# RescueMe.net
KiCad netlist of a schematic drawn in EAGLE
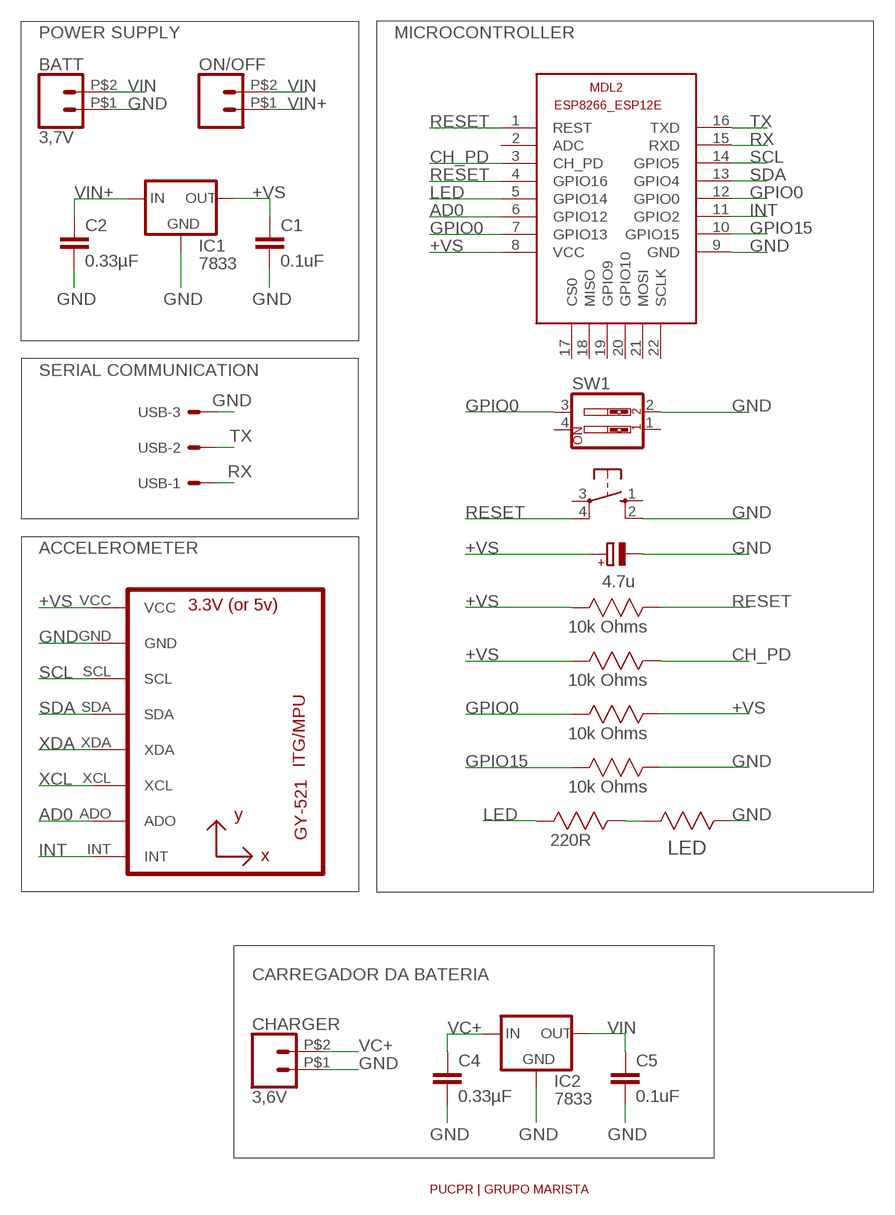
[diagram p0: schematic, sheet 1]

(export (version "E")
  (design (tool "Eeschema 10.0.6"))
  (components
    (comp (ref "BATT")
      (value "3,7V")
      (footprint "eagle-import:1X02_BIG")
      (libsource (lib "eagle-import") (part "CONN_02PTH2"))
    )
    (comp (ref "C1")
      (value "0.1uF")
      (footprint "eagle-import:0805")
      (libsource (lib "eagle-import") (part "0.33UF/330NF-0805-50V-10%"))
    )
    (comp (ref "C2")
      (value "0.33µF")
      (footprint "eagle-import:0805")
      (libsource (lib "eagle-import") (part "0.33UF/330NF-0805-50V-10%"))
    )
    (comp (ref "C4")
      (value "0.33µF")
      (footprint "eagle-import:0805")
      (libsource (lib "eagle-import") (part "0.33UF/330NF-0805-50V-10%"))
    )
    (comp (ref "C5")
      (value "0.1uF")
      (footprint "eagle-import:0805")
      (libsource (lib "eagle-import") (part "0.33UF/330NF-0805-50V-10%"))
    )
    (comp (ref "C7")
      (value "4.7u")
      (footprint "eagle-import:153CLV-0405")
      (libsource (lib "eagle-import") (part "CPOL-EU153CLV-0405"))
    )
    (comp (ref "CHARGER")
      (value "3,6V")
      (footprint "eagle-import:1X02_BIG")
      (libsource (lib "eagle-import") (part "CONN_02PTH2"))
    )
    (comp (ref "IC1")
      (value "7833")
      (footprint "eagle-import:78XXS")
      (libsource (lib "eagle-import") (part "78XXS"))
    )
    (comp (ref "IC2")
      (value "7833")
      (footprint "eagle-import:78XXS")
      (libsource (lib "eagle-import") (part "78XXS"))
    )
    (comp (ref "LED")
      (value "ERA-6AEB221V")
      (footprint "eagle-import:RESC2013X65N")
      (fields (field (name "TOLERANCE") "±0.1 %"))
      (libsource (lib "eagle-import") (part "ERA-6AEB221V"))
    )
    (comp (ref "MDL2")
      (value "ESP8266")
      (footprint "eagle-import:ESP8266-ESP12E")
      (fields (field (name "MPN") "317060015"))
      (libsource (lib "eagle-import") (part "ESP8266-12EESP8266-ESP12E"))
    )
    (comp (ref "ON/OFF")
      (value "CONN_02PTH2")
      (footprint "eagle-import:1X02_BIG")
      (libsource (lib "eagle-import") (part "CONN_02PTH2"))
    )
    (comp (ref "R_CHPD")
      (value "10k Ohms")
      (footprint "eagle-import:RESC2013X65N")
      (fields (field (name "MPN") "ERA6AEB103V") (field (name "TOLERANCE") "±0.1 %"))
      (libsource (lib "eagle-import") (part "ERA6AEB103V"))
    )
    (comp (ref "R_G0")
      (value "10k Ohms")
      (footprint "eagle-import:RESC2013X65N")
      (fields (field (name "MPN") "ERA6AEB103V") (field (name "TOLERANCE") "±0.1 %"))
      (libsource (lib "eagle-import") (part "ERA6AEB103V"))
    )
    (comp (ref "R_G15")
      (value "10k Ohms")
      (footprint "eagle-import:RESC2013X65N")
      (fields (field (name "MPN") "ERA6AEB103V") (field (name "TOLERANCE") "±0.1 %"))
      (libsource (lib "eagle-import") (part "ERA6AEB103V"))
    )
    (comp (ref "R_LED")
      (value "220R")
      (footprint "eagle-import:RESC2013X65N")
      (fields (field (name "MPN") "ERA-6AEB221V") (field (name "TOLERANCE") "±0.1 %"))
      (libsource (lib "eagle-import") (part "ERA-6AEB221V"))
    )
    (comp (ref "R_RST")
      (value "10k Ohms")
      (footprint "eagle-import:RESC2013X65N")
      (fields (field (name "MPN") "ERA6AEB103V") (field (name "TOLERANCE") "±0.1 %"))
      (libsource (lib "eagle-import") (part "ERA6AEB103V"))
    )
    (comp (ref "S1")
      (value "10-XX")
      (footprint "eagle-import:B3F-10XX")
      (fields (field (name "MPN") "B3F-1000"))
      (libsource (lib "eagle-import") (part "10-XX"))
    )
    (comp (ref "SW1")
      (value "SW_DIP-2")
      (footprint "eagle-import:DIPSWITCH-02")
      (libsource (lib "eagle-import") (part "SW_DIP-2"))
    )
    (comp (ref "U$1")
      (value "PUCPR_G")
      (footprint "eagle-import:PUCPR")
      (libsource (lib "eagle-import") (part "PUCPR_G"))
    )
    (comp (ref "U1")
      (value "GY-521MPU6050")
      (footprint "eagle-import:GY-521")
      (libsource (lib "eagle-import") (part "GY-521MPU6050"))
    )
    (comp (ref "USB")
      (value "22-27-2031-03")
      (footprint "eagle-import:6410-03")
      (libsource (lib "eagle-import") (part "22-?-0327-2031"))
    )
  )
  (nets
    (net (code "1") (name "/+VS") (class "Default")
      (node (ref "C1") (pin "1") (pinfunction "1_1") (pintype "passive"))
      (node (ref "C7") (pin "+") (pinfunction "+_+") (pintype "passive"))
      (node (ref "IC1") (pin "OUT") (pinfunction "OUT_OUT") (pintype "passive"))
      (node (ref "MDL2") (pin "8") (pinfunction "VCC_8") (pintype "bidirectional"))
      (node (ref "R_CHPD") (pin "2") (pinfunction "R2_2") (pintype "passive"))
      (node (ref "R_G0") (pin "1") (pinfunction "R1_1") (pintype "passive"))
      (node (ref "R_RST") (pin "2") (pinfunction "R2_2") (pintype "passive"))
      (node (ref "U1") (pin "VCC") (pinfunction "VCC_VCC") (pintype "bidirectional"))
    )
    (net (code "2") (name "/AD0") (class "Default")
      (node (ref "MDL2") (pin "6") (pinfunction "GPIO12_6") (pintype "bidirectional"))
      (node (ref "U1") (pin "ADO") (pinfunction "ADO_ADO") (pintype "bidirectional"))
    )
    (net (code "3") (name "/CH_PD") (class "Default")
      (node (ref "MDL2") (pin "3") (pinfunction "CH_PD_3") (pintype "bidirectional"))
      (node (ref "R_CHPD") (pin "1") (pinfunction "R1_1") (pintype "passive"))
    )
    (net (code "4") (name "/GND") (class "Default")
      (node (ref "BATT") (pin "P$1") (pinfunction "1_P$1") (pintype "passive"))
      (node (ref "C1") (pin "2") (pinfunction "2_2") (pintype "passive"))
      (node (ref "C2") (pin "2") (pinfunction "2_2") (pintype "passive"))
      (node (ref "C4") (pin "2") (pinfunction "2_2") (pintype "passive"))
      (node (ref "C5") (pin "2") (pinfunction "2_2") (pintype "passive"))
      (node (ref "C7") (pin "-") (pinfunction "-_-") (pintype "passive"))
      (node (ref "CHARGER") (pin "P$1") (pinfunction "1_P$1") (pintype "passive"))
      (node (ref "IC1") (pin "GND") (pinfunction "GND_GND") (pintype "input"))
      (node (ref "IC2") (pin "GND") (pinfunction "GND_GND") (pintype "input"))
      (node (ref "LED") (pin "1") (pinfunction "R1_1") (pintype "passive"))
      (node (ref "MDL2") (pin "9") (pinfunction "GND_9") (pintype "bidirectional"))
      (node (ref "R_G15") (pin "1") (pinfunction "R1_1") (pintype "passive"))
      (node (ref "S1") (pin "2") (pinfunction "S1_2") (pintype "passive"))
      (node (ref "SW1") (pin "2") (pinfunction "2_2") (pintype "passive"))
      (node (ref "U1") (pin "GND") (pinfunction "GND_GND") (pintype "bidirectional"))
      (node (ref "USB") (pin "3") (pinfunction "S_3") (pintype "passive"))
    )
    (net (code "5") (name "/GPIO0") (class "Default")
      (node (ref "MDL2") (pin "12") (pinfunction "GPIO0_12") (pintype "bidirectional"))
      (node (ref "MDL2") (pin "7") (pinfunction "GPIO13_7") (pintype "bidirectional"))
      (node (ref "R_G0") (pin "2") (pinfunction "R2_2") (pintype "passive"))
      (node (ref "SW1") (pin "3") (pinfunction "3_3") (pintype "passive"))
    )
    (net (code "6") (name "/GPIO15") (class "Default")
      (node (ref "MDL2") (pin "10") (pinfunction "GPIO15_10") (pintype "bidirectional"))
      (node (ref "R_G15") (pin "2") (pinfunction "R2_2") (pintype "passive"))
    )
    (net (code "7") (name "/INT") (class "Default")
      (node (ref "MDL2") (pin "11") (pinfunction "GPIO2_11") (pintype "bidirectional"))
      (node (ref "U1") (pin "INT") (pinfunction "INT_INT") (pintype "bidirectional"))
    )
    (net (code "8") (name "/LED") (class "Default")
      (node (ref "MDL2") (pin "5") (pinfunction "GPIO14_5") (pintype "bidirectional"))
      (node (ref "R_LED") (pin "2") (pinfunction "R2_2") (pintype "passive"))
    )
    (net (code "9") (name "/RESET") (class "Default")
      (node (ref "MDL2") (pin "1") (pinfunction "REST_1") (pintype "bidirectional"))
      (node (ref "MDL2") (pin "4") (pinfunction "GPIO16_4") (pintype "bidirectional"))
      (node (ref "R_RST") (pin "1") (pinfunction "R1_1") (pintype "passive"))
      (node (ref "S1") (pin "4") (pinfunction "P1_4") (pintype "passive"))
    )
    (net (code "10") (name "/RX") (class "Default")
      (node (ref "MDL2") (pin "15") (pinfunction "RXD_15") (pintype "bidirectional"))
      (node (ref "USB") (pin "1") (pinfunction "S_1") (pintype "passive"))
    )
    (net (code "11") (name "/SCL") (class "Default")
      (node (ref "MDL2") (pin "14") (pinfunction "GPIO5_14") (pintype "bidirectional"))
      (node (ref "U1") (pin "SCL") (pinfunction "SCL_SCL") (pintype "bidirectional"))
    )
    (net (code "12") (name "/SDA") (class "Default")
      (node (ref "MDL2") (pin "13") (pinfunction "GPIO4_13") (pintype "bidirectional"))
      (node (ref "U1") (pin "SDA") (pinfunction "SDA_SDA") (pintype "bidirectional"))
    )
    (net (code "13") (name "/TX") (class "Default")
      (node (ref "MDL2") (pin "16") (pinfunction "TXD_16") (pintype "bidirectional"))
      (node (ref "USB") (pin "2") (pinfunction "S_2") (pintype "passive"))
    )
    (net (code "14") (name "/VC+") (class "Default")
      (node (ref "C4") (pin "1") (pinfunction "1_1") (pintype "passive"))
      (node (ref "CHARGER") (pin "P$2") (pinfunction "2_P$2") (pintype "passive"))
      (node (ref "IC2") (pin "IN") (pinfunction "IN_IN") (pintype "input"))
    )
    (net (code "15") (name "/VIN") (class "Default")
      (node (ref "BATT") (pin "P$2") (pinfunction "2_P$2") (pintype "passive"))
      (node (ref "C5") (pin "1") (pinfunction "1_1") (pintype "passive"))
      (node (ref "IC2") (pin "OUT") (pinfunction "OUT_OUT") (pintype "passive"))
      (node (ref "ON/OFF") (pin "P$2") (pinfunction "2_P$2") (pintype "passive"))
    )
    (net (code "16") (name "/VIN+") (class "Default")
      (node (ref "C2") (pin "1") (pinfunction "1_1") (pintype "passive"))
      (node (ref "IC1") (pin "IN") (pinfunction "IN_IN") (pintype "input"))
      (node (ref "ON/OFF") (pin "P$1") (pinfunction "1_P$1") (pintype "passive"))
    )
    (net (code "17") (name "/XCL") (class "Default")
      (node (ref "U1") (pin "XCL") (pinfunction "XCL_XCL") (pintype "bidirectional"))
    )
    (net (code "18") (name "/XDA") (class "Default")
      (node (ref "U1") (pin "XDA") (pinfunction "XDA_XDA") (pintype "bidirectional"))
    )
    (net (code "19") (name "Net-(LED-R2)") (class "Default")
      (node (ref "LED") (pin "2") (pinfunction "R2_2") (pintype "passive"))
      (node (ref "R_LED") (pin "1") (pinfunction "R1_1") (pintype "passive"))
    )
    (net (code "20") (name "unconnected-(MDL2-ADC-Pad2)") (class "Default")
      (node (ref "MDL2") (pin "2") (pinfunction "ADC_2") (pintype "bidirectional"))
    )
    (net (code "21") (name "unconnected-(MDL2-CS0-Pad17)") (class "Default")
      (node (ref "MDL2") (pin "17") (pinfunction "CS0_17") (pintype "bidirectional"))
    )
    (net (code "22") (name "unconnected-(MDL2-GPIO9-Pad19)") (class "Default")
      (node (ref "MDL2") (pin "19") (pinfunction "GPIO9_19") (pintype "bidirectional"))
    )
    (net (code "23") (name "unconnected-(MDL2-GPIO10-Pad20)") (class "Default")
      (node (ref "MDL2") (pin "20") (pinfunction "GPIO10_20") (pintype "bidirectional"))
    )
    (net (code "24") (name "unconnected-(MDL2-MISO-Pad18)") (class "Default")
      (node (ref "MDL2") (pin "18") (pinfunction "MISO_18") (pintype "bidirectional"))
    )
    (net (code "25") (name "unconnected-(MDL2-MOSI-Pad21)") (class "Default")
      (node (ref "MDL2") (pin "21") (pinfunction "MOSI_21") (pintype "bidirectional"))
    )
    (net (code "26") (name "unconnected-(MDL2-SCLK-Pad22)") (class "Default")
      (node (ref "MDL2") (pin "22") (pinfunction "SCLK_22") (pintype "bidirectional"))
    )
    (net (code "27") (name "unconnected-(S1-P-Pad3)") (class "Default")
      (node (ref "S1") (pin "3") (pinfunction "P_3") (pintype "passive"))
    )
    (net (code "28") (name "unconnected-(S1-S-Pad1)") (class "Default")
      (node (ref "S1") (pin "1") (pinfunction "S_1") (pintype "passive"))
    )
    (net (code "29") (name "unconnected-(SW1-Pad1)") (class "Default")
      (node (ref "SW1") (pin "1") (pinfunction "1_1") (pintype "passive"))
    )
    (net (code "30") (name "unconnected-(SW1-Pad4)") (class "Default")
      (node (ref "SW1") (pin "4") (pinfunction "4_4") (pintype "passive"))
    )
  )
)
